# NOT-A.net
KiCad netlist of a schematic drawn in EAGLE
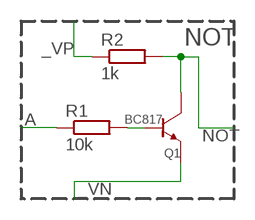
[diagram p0: schematic, sheet 1]

(export (version "E")
  (design (tool "Eeschema 10.0.6"))
  (components
    (comp (ref "Q1")
      (value "BC817")
      (footprint "eagle-import:SOT23")
      (libsource (lib "eagle-import") (part "TRANSISTOR-NPN-GENERIC-SOT23-BECDEFAULT"))
    )
    (comp (ref "R1")
      (value "10k")
      (footprint "eagle-import:R0603")
      (libsource (lib "eagle-import") (part "R-EU_R0603"))
    )
    (comp (ref "R2")
      (value "1k")
      (footprint "eagle-import:R0603")
      (libsource (lib "eagle-import") (part "R-EU_R0603"))
    )
  )
  (nets
    (net (code "1") (name "/A") (class "Default")
      (node (ref "R1") (pin "1") (pinfunction "1_1") (pintype "passive"))
    )
    (net (code "2") (name "/NOT") (class "Default")
      (node (ref "Q1") (pin "P$3") (pinfunction "COLLECTOR_P$3") (pintype "bidirectional"))
      (node (ref "R2") (pin "2") (pinfunction "2_2") (pintype "passive"))
    )
    (net (code "3") (name "/_VN") (class "Default")
      (node (ref "Q1") (pin "P$2") (pinfunction "EMITTER_P$2") (pintype "bidirectional"))
    )
    (net (code "4") (name "/_VP") (class "Default")
      (node (ref "R2") (pin "1") (pinfunction "1_1") (pintype "passive"))
    )
    (net (code "5") (name "Net-(Q1-BASE)") (class "Default")
      (node (ref "Q1") (pin "P$1") (pinfunction "BASE_P$1") (pintype "bidirectional"))
      (node (ref "R1") (pin "2") (pinfunction "2_2") (pintype "passive"))
    )
  )
)
